# motor_driver_module.net
KiCad netlist of a schematic drawn in EAGLE
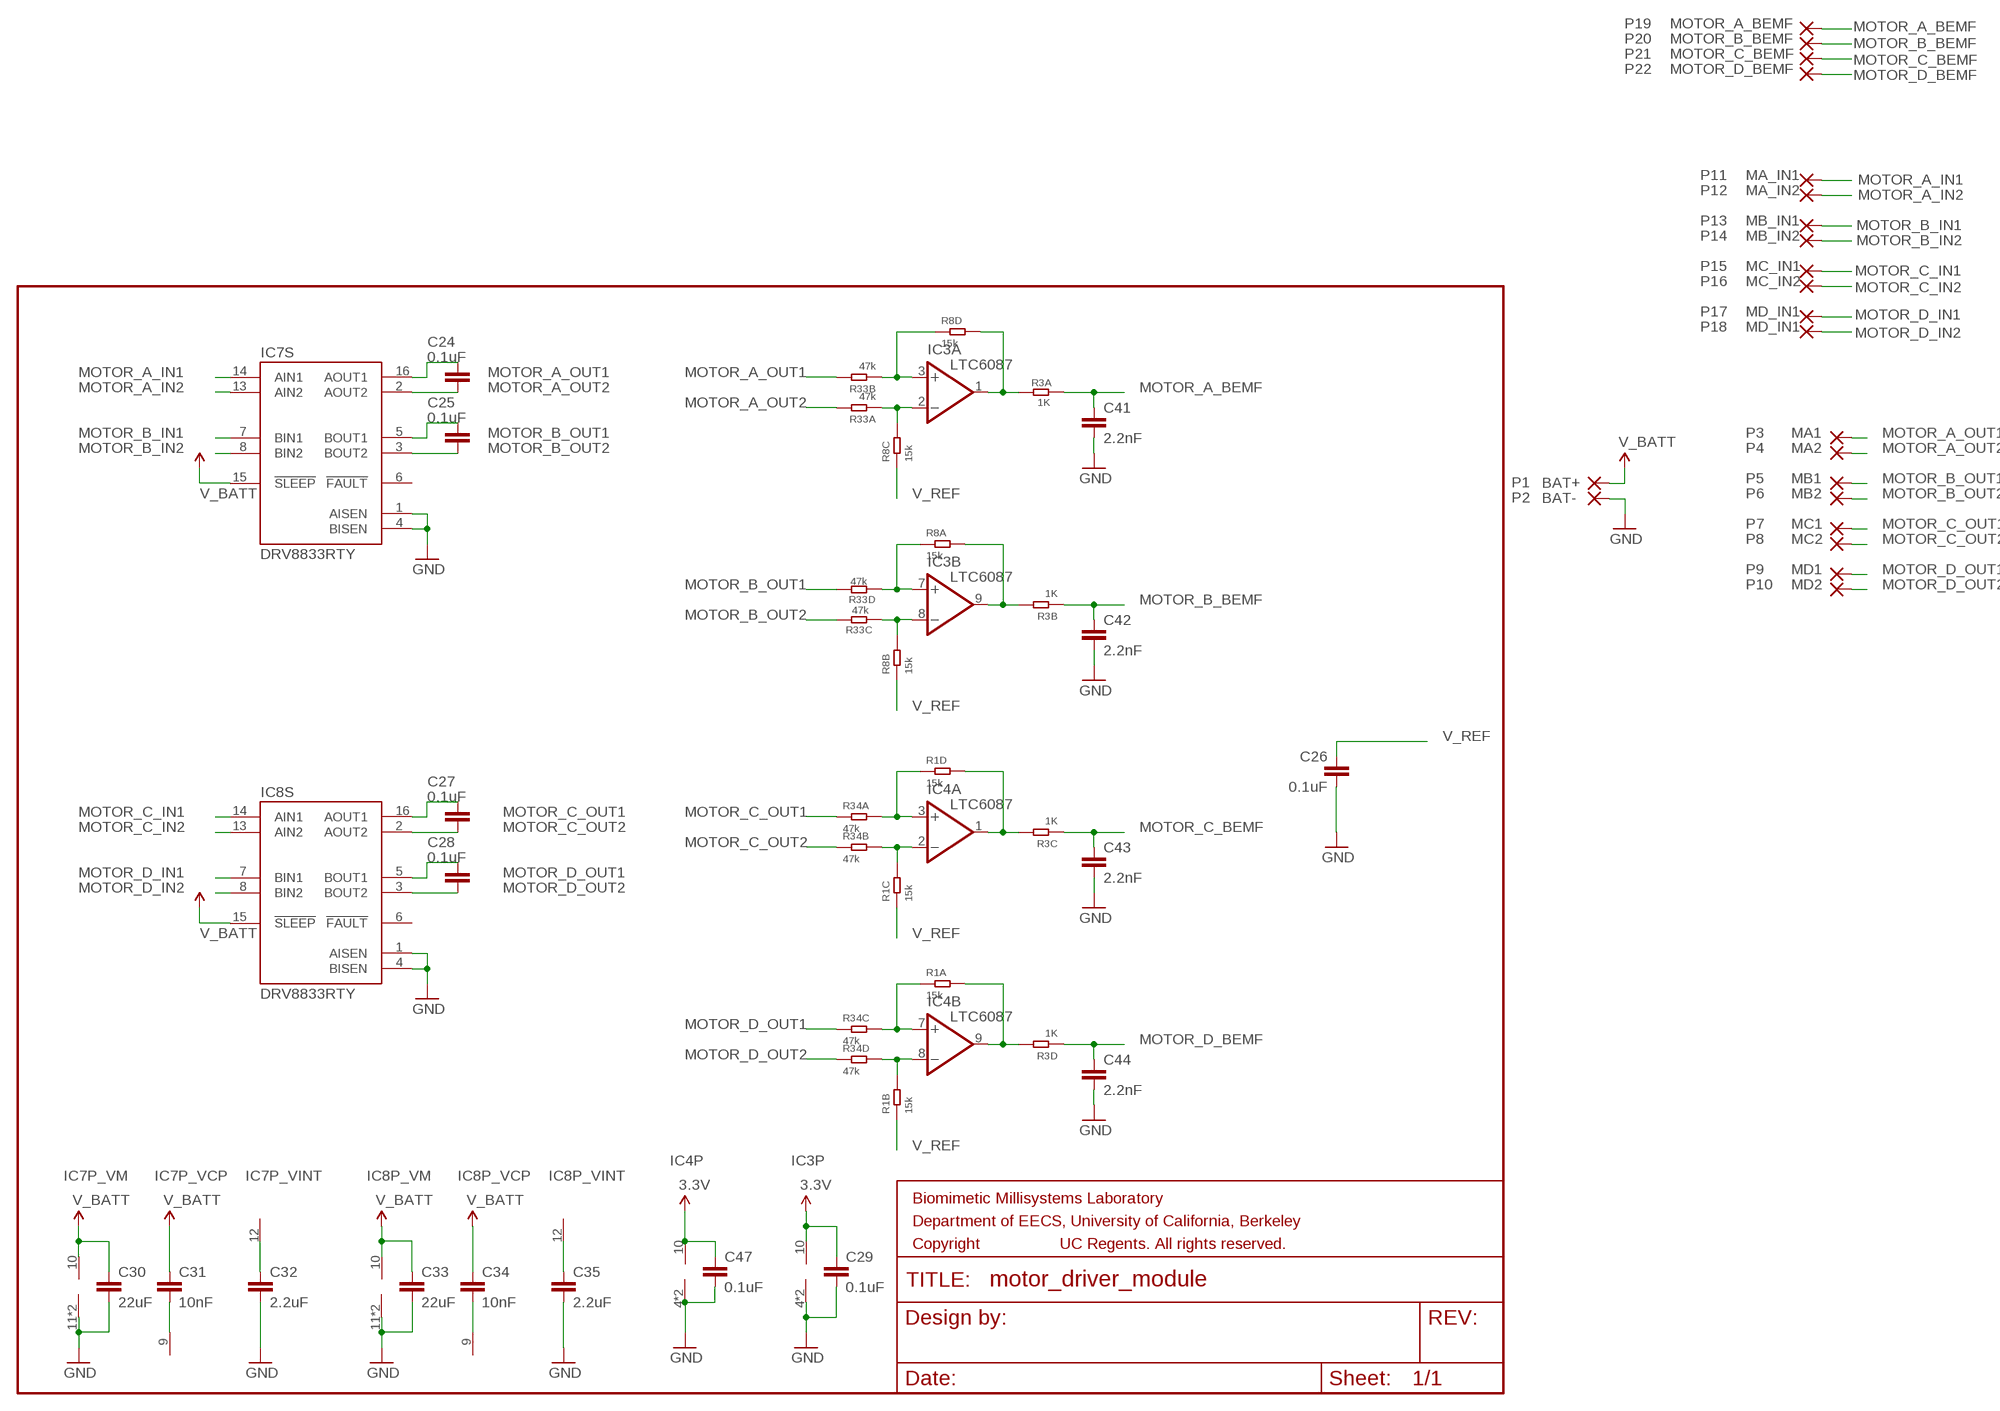
[diagram p0: schematic, sheet 1]

(export (version "E")
  (design (tool "Eeschema 10.0.6"))
  (components
    (comp (ref "C24")
      (value "0.1uF")
      (footprint "eagle-import:0402-CAP")
      (fields (field (name "VOLTAGE") "10V"))
      (libsource (lib "eagle-import") (part "CAP0402-CAP"))
    )
    (comp (ref "C25")
      (value "0.1uF")
      (footprint "eagle-import:0402-CAP")
      (fields (field (name "VOLTAGE") "10V"))
      (libsource (lib "eagle-import") (part "CAP0402-CAP"))
    )
    (comp (ref "C26")
      (value "0.1uF")
      (footprint "eagle-import:0402-CAP")
      (libsource (lib "eagle-import") (part "CAP0402-CAP"))
    )
    (comp (ref "C27")
      (value "0.1uF")
      (footprint "eagle-import:0402-CAP")
      (fields (field (name "VOLTAGE") "10V"))
      (libsource (lib "eagle-import") (part "CAP0402-CAP"))
    )
    (comp (ref "C28")
      (value "0.1uF")
      (footprint "eagle-import:0402-CAP")
      (fields (field (name "VOLTAGE") "10V"))
      (libsource (lib "eagle-import") (part "CAP0402-CAP"))
    )
    (comp (ref "C29")
      (value "0.1uF")
      (footprint "eagle-import:0402-CAP")
      (libsource (lib "eagle-import") (part "CAP0402-CAP"))
    )
    (comp (ref "C30")
      (value "22uF")
      (footprint "eagle-import:0603-CAP")
      (libsource (lib "eagle-import") (part "CAP0603-CAP"))
    )
    (comp (ref "C31")
      (value "10nF")
      (footprint "eagle-import:0402-CAP")
      (fields (field (name "VOLTAGE") "16V"))
      (libsource (lib "eagle-import") (part "CAP0402-CAP"))
    )
    (comp (ref "C32")
      (value "2.2uF")
      (footprint "eagle-import:0402-CAP")
      (fields (field (name "VOLTAGE") "6.3V"))
      (libsource (lib "eagle-import") (part "CAP0402-CAP"))
    )
    (comp (ref "C33")
      (value "22uF")
      (footprint "eagle-import:0603-CAP")
      (libsource (lib "eagle-import") (part "CAP0603-CAP"))
    )
    (comp (ref "C34")
      (value "10nF")
      (footprint "eagle-import:0402-CAP")
      (fields (field (name "VOLTAGE") "16V"))
      (libsource (lib "eagle-import") (part "CAP0402-CAP"))
    )
    (comp (ref "C35")
      (value "2.2uF")
      (footprint "eagle-import:0402-CAP")
      (fields (field (name "VOLTAGE") "6.3V"))
      (libsource (lib "eagle-import") (part "CAP0402-CAP"))
    )
    (comp (ref "C41")
      (value "2.2nF")
      (footprint "eagle-import:0402-CAP")
      (libsource (lib "eagle-import") (part "CAP0402-CAP"))
    )
    (comp (ref "C42")
      (value "2.2nF")
      (footprint "eagle-import:0402-CAP")
      (libsource (lib "eagle-import") (part "CAP0402-CAP"))
    )
    (comp (ref "C43")
      (value "2.2nF")
      (footprint "eagle-import:0402-CAP")
      (libsource (lib "eagle-import") (part "CAP0402-CAP"))
    )
    (comp (ref "C44")
      (value "2.2nF")
      (footprint "eagle-import:0402-CAP")
      (libsource (lib "eagle-import") (part "CAP0402-CAP"))
    )
    (comp (ref "C47")
      (value "0.1uF")
      (footprint "eagle-import:0402-CAP")
      (libsource (lib "eagle-import") (part "CAP0402-CAP"))
    )
    (comp (ref "IC3")
      (value "LTC6087")
      (footprint "eagle-import:DFN-10")
      (libsource (lib "eagle-import") (part "LTC6087"))
    )
    (comp (ref "IC4")
      (value "LTC6087")
      (footprint "eagle-import:DFN-10")
      (libsource (lib "eagle-import") (part "LTC6087"))
    )
    (comp (ref "IC7")
      (value "DRV8833RTY")
      (footprint "eagle-import:S-PWQFN-N16")
      (libsource (lib "eagle-import") (part "DRV8833RTY"))
    )
    (comp (ref "IC8")
      (value "DRV8833RTY")
      (footprint "eagle-import:S-PWQFN-N16")
      (libsource (lib "eagle-import") (part "DRV8833RTY"))
    )
    (comp (ref "P1")
      (value "BAT+")
      (footprint "eagle-import:SMD1,27-2,54")
      (libsource (lib "eagle-import") (part "SMD2"))
    )
    (comp (ref "P2")
      (value "BAT-")
      (footprint "eagle-import:SMD1,27-2,54")
      (libsource (lib "eagle-import") (part "SMD2"))
    )
    (comp (ref "P3")
      (value "MA1")
      (footprint "eagle-import:SMD1,27-2,54")
      (libsource (lib "eagle-import") (part "SMD2"))
    )
    (comp (ref "P4")
      (value "MA2")
      (footprint "eagle-import:SMD1,27-2,54")
      (libsource (lib "eagle-import") (part "SMD2"))
    )
    (comp (ref "P5")
      (value "MB1")
      (footprint "eagle-import:SMD1,27-2,54")
      (libsource (lib "eagle-import") (part "SMD2"))
    )
    (comp (ref "P6")
      (value "MB2")
      (footprint "eagle-import:SMD1,27-2,54")
      (libsource (lib "eagle-import") (part "SMD2"))
    )
    (comp (ref "P7")
      (value "MC1")
      (footprint "eagle-import:SMD1,27-2,54")
      (libsource (lib "eagle-import") (part "SMD2"))
    )
    (comp (ref "P8")
      (value "MC2")
      (footprint "eagle-import:SMD1,27-2,54")
      (libsource (lib "eagle-import") (part "SMD2"))
    )
    (comp (ref "P9")
      (value "MD1")
      (footprint "eagle-import:SMD1,27-2,54")
      (libsource (lib "eagle-import") (part "SMD2"))
    )
    (comp (ref "P10")
      (value "MD2")
      (footprint "eagle-import:SMD1,27-2,54")
      (libsource (lib "eagle-import") (part "SMD2"))
    )
    (comp (ref "P11")
      (value "MA_IN1")
      (footprint "eagle-import:SMD1,27-2,54")
      (libsource (lib "eagle-import") (part "SMD2"))
    )
    (comp (ref "P12")
      (value "MA_IN2")
      (footprint "eagle-import:SMD1,27-2,54")
      (libsource (lib "eagle-import") (part "SMD2"))
    )
    (comp (ref "P13")
      (value "MB_IN1")
      (footprint "eagle-import:SMD1,27-2,54")
      (libsource (lib "eagle-import") (part "SMD2"))
    )
    (comp (ref "P14")
      (value "MB_IN2")
      (footprint "eagle-import:SMD1,27-2,54")
      (libsource (lib "eagle-import") (part "SMD2"))
    )
    (comp (ref "P15")
      (value "MC_IN1")
      (footprint "eagle-import:SMD1,27-2,54")
      (libsource (lib "eagle-import") (part "SMD2"))
    )
    (comp (ref "P16")
      (value "MC_IN2")
      (footprint "eagle-import:SMD1,27-2,54")
      (libsource (lib "eagle-import") (part "SMD2"))
    )
    (comp (ref "P17")
      (value "MD_IN1")
      (footprint "eagle-import:SMD1,27-2,54")
      (libsource (lib "eagle-import") (part "SMD2"))
    )
    (comp (ref "P18")
      (value "MD_IN1")
      (footprint "eagle-import:SMD1,27-2,54")
      (libsource (lib "eagle-import") (part "SMD2"))
    )
    (comp (ref "P19")
      (value "MOTOR_A_BEMF")
      (footprint "eagle-import:SMD1,27-2,54")
      (libsource (lib "eagle-import") (part "SMD2"))
    )
    (comp (ref "P20")
      (value "MOTOR_B_BEMF")
      (footprint "eagle-import:SMD1,27-2,54")
      (libsource (lib "eagle-import") (part "SMD2"))
    )
    (comp (ref "P21")
      (value "MOTOR_C_BEMF")
      (footprint "eagle-import:SMD1,27-2,54")
      (libsource (lib "eagle-import") (part "SMD2"))
    )
    (comp (ref "P22")
      (value "MOTOR_D_BEMF")
      (footprint "eagle-import:SMD1,27-2,54")
      (libsource (lib "eagle-import") (part "SMD2"))
    )
    (comp (ref "R1")
      (value "15k")
      (footprint "eagle-import:R1206-8")
      (libsource (lib "eagle-import") (part "R-4R"))
    )
    (comp (ref "R3")
      (value "1K")
      (footprint "eagle-import:R1206-8")
      (libsource (lib "eagle-import") (part "R-4R"))
    )
    (comp (ref "R8")
      (value "15k")
      (footprint "eagle-import:R1206-8")
      (libsource (lib "eagle-import") (part "R-4R"))
    )
    (comp (ref "R33")
      (value "47k")
      (footprint "eagle-import:R1206-8")
      (libsource (lib "eagle-import") (part "R-4R"))
    )
    (comp (ref "R34")
      (value "47k")
      (footprint "eagle-import:R1206-8")
      (libsource (lib "eagle-import") (part "R-4R"))
    )
  )
  (nets
    (net (code "1") (name "/MOTOR_A_BEMF") (class "Default")
      (node (ref "C41") (pin "1") (pinfunction "1_1") (pintype "passive"))
      (node (ref "P19") (pin "1") (pinfunction "P_1") (pintype "passive"))
      (node (ref "R3") (pin "1") (pinfunction "1_1") (pintype "passive"))
    )
    (net (code "2") (name "/MOTOR_A_IN1") (class "Default")
      (node (ref "IC7") (pin "14") (pinfunction "AIN1_14") (pintype "bidirectional"))
      (node (ref "P11") (pin "1") (pinfunction "P_1") (pintype "passive"))
    )
    (net (code "3") (name "/MOTOR_A_IN2") (class "Default")
      (node (ref "IC7") (pin "13") (pinfunction "AIN2_13") (pintype "bidirectional"))
      (node (ref "P12") (pin "1") (pinfunction "P_1") (pintype "passive"))
    )
    (net (code "4") (name "/MOTOR_A_OUT1") (class "Default")
      (node (ref "C24") (pin "1") (pinfunction "1_1") (pintype "passive"))
      (node (ref "IC7") (pin "16") (pinfunction "AOUT1_16") (pintype "bidirectional"))
      (node (ref "P3") (pin "1") (pinfunction "P_1") (pintype "passive"))
      (node (ref "R33") (pin "7") (pinfunction "2_7") (pintype "passive"))
    )
    (net (code "5") (name "/MOTOR_A_OUT2") (class "Default")
      (node (ref "C24") (pin "2") (pinfunction "2_2") (pintype "passive"))
      (node (ref "IC7") (pin "2") (pinfunction "AOUT2_2") (pintype "bidirectional"))
      (node (ref "P4") (pin "1") (pinfunction "P_1") (pintype "passive"))
      (node (ref "R33") (pin "8") (pinfunction "2_8") (pintype "passive"))
    )
    (net (code "6") (name "/MOTOR_B_BEMF") (class "Default")
      (node (ref "C42") (pin "1") (pinfunction "1_1") (pintype "passive"))
      (node (ref "P20") (pin "1") (pinfunction "P_1") (pintype "passive"))
      (node (ref "R3") (pin "2") (pinfunction "1_2") (pintype "passive"))
    )
    (net (code "7") (name "/MOTOR_B_IN1") (class "Default")
      (node (ref "IC7") (pin "7") (pinfunction "BIN1_7") (pintype "bidirectional"))
      (node (ref "P13") (pin "1") (pinfunction "P_1") (pintype "passive"))
    )
    (net (code "8") (name "/MOTOR_B_IN2") (class "Default")
      (node (ref "IC7") (pin "8") (pinfunction "BIN2_8") (pintype "bidirectional"))
      (node (ref "P14") (pin "1") (pinfunction "P_1") (pintype "passive"))
    )
    (net (code "9") (name "/MOTOR_B_OUT1") (class "Default")
      (node (ref "C25") (pin "1") (pinfunction "1_1") (pintype "passive"))
      (node (ref "IC7") (pin "5") (pinfunction "BOUT1_5") (pintype "bidirectional"))
      (node (ref "P5") (pin "1") (pinfunction "P_1") (pintype "passive"))
      (node (ref "R33") (pin "4") (pinfunction "1_4") (pintype "passive"))
    )
    (net (code "10") (name "/MOTOR_B_OUT2") (class "Default")
      (node (ref "C25") (pin "2") (pinfunction "2_2") (pintype "passive"))
      (node (ref "IC7") (pin "3") (pinfunction "BOUT2_3") (pintype "bidirectional"))
      (node (ref "P6") (pin "1") (pinfunction "P_1") (pintype "passive"))
      (node (ref "R33") (pin "3") (pinfunction "1_3") (pintype "passive"))
    )
    (net (code "11") (name "/MOTOR_C_BEMF") (class "Default")
      (node (ref "C43") (pin "1") (pinfunction "1_1") (pintype "passive"))
      (node (ref "P21") (pin "1") (pinfunction "P_1") (pintype "passive"))
      (node (ref "R3") (pin "3") (pinfunction "1_3") (pintype "passive"))
    )
    (net (code "12") (name "/MOTOR_C_IN1") (class "Default")
      (node (ref "IC8") (pin "14") (pinfunction "AIN1_14") (pintype "bidirectional"))
      (node (ref "P15") (pin "1") (pinfunction "P_1") (pintype "passive"))
    )
    (net (code "13") (name "/MOTOR_C_IN2") (class "Default")
      (node (ref "IC8") (pin "13") (pinfunction "AIN2_13") (pintype "bidirectional"))
      (node (ref "P16") (pin "1") (pinfunction "P_1") (pintype "passive"))
    )
    (net (code "14") (name "/MOTOR_C_OUT1") (class "Default")
      (node (ref "C27") (pin "1") (pinfunction "1_1") (pintype "passive"))
      (node (ref "IC8") (pin "16") (pinfunction "AOUT1_16") (pintype "bidirectional"))
      (node (ref "P7") (pin "1") (pinfunction "P_1") (pintype "passive"))
      (node (ref "R34") (pin "1") (pinfunction "1_1") (pintype "passive"))
    )
    (net (code "15") (name "/MOTOR_C_OUT2") (class "Default")
      (node (ref "C27") (pin "2") (pinfunction "2_2") (pintype "passive"))
      (node (ref "IC8") (pin "2") (pinfunction "AOUT2_2") (pintype "bidirectional"))
      (node (ref "P8") (pin "1") (pinfunction "P_1") (pintype "passive"))
      (node (ref "R34") (pin "2") (pinfunction "1_2") (pintype "passive"))
    )
    (net (code "16") (name "/MOTOR_D_BEMF") (class "Default")
      (node (ref "C44") (pin "1") (pinfunction "1_1") (pintype "passive"))
      (node (ref "P22") (pin "1") (pinfunction "P_1") (pintype "passive"))
      (node (ref "R3") (pin "4") (pinfunction "1_4") (pintype "passive"))
    )
    (net (code "17") (name "/MOTOR_D_IN1") (class "Default")
      (node (ref "IC8") (pin "7") (pinfunction "BIN1_7") (pintype "bidirectional"))
      (node (ref "P17") (pin "1") (pinfunction "P_1") (pintype "passive"))
    )
    (net (code "18") (name "/MOTOR_D_IN2") (class "Default")
      (node (ref "IC8") (pin "8") (pinfunction "BIN2_8") (pintype "bidirectional"))
      (node (ref "P18") (pin "1") (pinfunction "P_1") (pintype "passive"))
    )
    (net (code "19") (name "/MOTOR_D_OUT1") (class "Default")
      (node (ref "C28") (pin "1") (pinfunction "1_1") (pintype "passive"))
      (node (ref "IC8") (pin "5") (pinfunction "BOUT1_5") (pintype "bidirectional"))
      (node (ref "P9") (pin "1") (pinfunction "P_1") (pintype "passive"))
      (node (ref "R34") (pin "3") (pinfunction "1_3") (pintype "passive"))
    )
    (net (code "20") (name "/MOTOR_D_OUT2") (class "Default")
      (node (ref "C28") (pin "2") (pinfunction "2_2") (pintype "passive"))
      (node (ref "IC8") (pin "3") (pinfunction "BOUT2_3") (pintype "bidirectional"))
      (node (ref "P10") (pin "1") (pinfunction "P_1") (pintype "passive"))
      (node (ref "R34") (pin "4") (pinfunction "1_4") (pintype "passive"))
    )
    (net (code "21") (name "/V_REF") (class "Default")
      (node (ref "C26") (pin "1") (pinfunction "1_1") (pintype "passive"))
      (node (ref "R1") (pin "2") (pinfunction "1_2") (pintype "passive"))
      (node (ref "R1") (pin "3") (pinfunction "1_3") (pintype "passive"))
      (node (ref "R8") (pin "2") (pinfunction "1_2") (pintype "passive"))
      (node (ref "R8") (pin "3") (pinfunction "1_3") (pintype "passive"))
    )
    (net (code "22") (name "3.3V") (class "Default")
      (node (ref "C29") (pin "1") (pinfunction "1_1") (pintype "passive"))
      (node (ref "C47") (pin "1") (pinfunction "1_1") (pintype "passive"))
      (node (ref "IC3") (pin "10") (pinfunction "V+_10") (pintype "power_in"))
      (node (ref "IC4") (pin "10") (pinfunction "V+_10") (pintype "power_in"))
    )
    (net (code "23") (name "GND") (class "Default")
      (node (ref "C26") (pin "2") (pinfunction "2_2") (pintype "passive"))
      (node (ref "C29") (pin "2") (pinfunction "2_2") (pintype "passive"))
      (node (ref "C30") (pin "2") (pinfunction "2_2") (pintype "passive"))
      (node (ref "C32") (pin "2") (pinfunction "2_2") (pintype "passive"))
      (node (ref "C33") (pin "2") (pinfunction "2_2") (pintype "passive"))
      (node (ref "C35") (pin "2") (pinfunction "2_2") (pintype "passive"))
      (node (ref "C41") (pin "2") (pinfunction "2_2") (pintype "passive"))
      (node (ref "C42") (pin "2") (pinfunction "2_2") (pintype "passive"))
      (node (ref "C43") (pin "2") (pinfunction "2_2") (pintype "passive"))
      (node (ref "C44") (pin "2") (pinfunction "2_2") (pintype "passive"))
      (node (ref "C47") (pin "2") (pinfunction "2_2") (pintype "passive"))
      (node (ref "IC3") (pin "4") (pinfunction "V-_4") (pintype "power_in"))
      (node (ref "IC3") (pin "PAD") (pinfunction "V-_PAD") (pintype "power_in"))
      (node (ref "IC4") (pin "4") (pinfunction "V-_4") (pintype "power_in"))
      (node (ref "IC4") (pin "PAD") (pinfunction "V-_PAD") (pintype "power_in"))
      (node (ref "IC7") (pin "1") (pinfunction "AISEN_1") (pintype "bidirectional"))
      (node (ref "IC7") (pin "11") (pinfunction "V-_11") (pintype "power_in"))
      (node (ref "IC7") (pin "4") (pinfunction "BISEN_4") (pintype "bidirectional"))
      (node (ref "IC7") (pin "PPAD") (pinfunction "V-_PPAD") (pintype "power_in"))
      (node (ref "IC8") (pin "1") (pinfunction "AISEN_1") (pintype "bidirectional"))
      (node (ref "IC8") (pin "11") (pinfunction "V-_11") (pintype "power_in"))
      (node (ref "IC8") (pin "4") (pinfunction "BISEN_4") (pintype "bidirectional"))
      (node (ref "IC8") (pin "PPAD") (pinfunction "V-_PPAD") (pintype "power_in"))
      (node (ref "P2") (pin "1") (pinfunction "P_1") (pintype "passive"))
    )
    (net (code "24") (name "Net-(IC3C-+IN)") (class "Default")
      (node (ref "IC3") (pin "3") (pinfunction "+IN_3") (pintype "input"))
      (node (ref "R33") (pin "2") (pinfunction "1_2") (pintype "passive"))
      (node (ref "R8") (pin "4") (pinfunction "1_4") (pintype "passive"))
    )
    (net (code "25") (name "Net-(IC3C--IN)") (class "Default")
      (node (ref "IC3") (pin "2") (pinfunction "-IN_2") (pintype "input"))
      (node (ref "R33") (pin "1") (pinfunction "1_1") (pintype "passive"))
      (node (ref "R8") (pin "6") (pinfunction "2_6") (pintype "passive"))
    )
    (net (code "26") (name "Net-(IC3C-OUT)") (class "Default")
      (node (ref "IC3") (pin "1") (pinfunction "OUT_1") (pintype "output"))
      (node (ref "R3") (pin "8") (pinfunction "2_8") (pintype "passive"))
      (node (ref "R8") (pin "5") (pinfunction "2_5") (pintype "passive"))
    )
    (net (code "27") (name "Net-(IC3D-+IN)") (class "Default")
      (node (ref "IC3") (pin "7") (pinfunction "+IN_7") (pintype "input"))
      (node (ref "R33") (pin "5") (pinfunction "2_5") (pintype "passive"))
      (node (ref "R8") (pin "1") (pinfunction "1_1") (pintype "passive"))
    )
    (net (code "28") (name "Net-(IC3D--IN)") (class "Default")
      (node (ref "IC3") (pin "8") (pinfunction "-IN_8") (pintype "input"))
      (node (ref "R33") (pin "6") (pinfunction "2_6") (pintype "passive"))
      (node (ref "R8") (pin "7") (pinfunction "2_7") (pintype "passive"))
    )
    (net (code "29") (name "Net-(IC3D-OUT)") (class "Default")
      (node (ref "IC3") (pin "9") (pinfunction "OUT_9") (pintype "output"))
      (node (ref "R3") (pin "7") (pinfunction "2_7") (pintype "passive"))
      (node (ref "R8") (pin "8") (pinfunction "2_8") (pintype "passive"))
    )
    (net (code "30") (name "Net-(IC4C-+IN)") (class "Default")
      (node (ref "IC4") (pin "3") (pinfunction "+IN_3") (pintype "input"))
      (node (ref "R1") (pin "4") (pinfunction "1_4") (pintype "passive"))
      (node (ref "R34") (pin "8") (pinfunction "2_8") (pintype "passive"))
    )
    (net (code "31") (name "Net-(IC4C--IN)") (class "Default")
      (node (ref "IC4") (pin "2") (pinfunction "-IN_2") (pintype "input"))
      (node (ref "R1") (pin "6") (pinfunction "2_6") (pintype "passive"))
      (node (ref "R34") (pin "7") (pinfunction "2_7") (pintype "passive"))
    )
    (net (code "32") (name "Net-(IC4C-OUT)") (class "Default")
      (node (ref "IC4") (pin "1") (pinfunction "OUT_1") (pintype "output"))
      (node (ref "R1") (pin "5") (pinfunction "2_5") (pintype "passive"))
      (node (ref "R3") (pin "6") (pinfunction "2_6") (pintype "passive"))
    )
    (net (code "33") (name "Net-(IC4D-+IN)") (class "Default")
      (node (ref "IC4") (pin "7") (pinfunction "+IN_7") (pintype "input"))
      (node (ref "R1") (pin "1") (pinfunction "1_1") (pintype "passive"))
      (node (ref "R34") (pin "6") (pinfunction "2_6") (pintype "passive"))
    )
    (net (code "34") (name "Net-(IC4D--IN)") (class "Default")
      (node (ref "IC4") (pin "8") (pinfunction "-IN_8") (pintype "input"))
      (node (ref "R1") (pin "7") (pinfunction "2_7") (pintype "passive"))
      (node (ref "R34") (pin "5") (pinfunction "2_5") (pintype "passive"))
    )
    (net (code "35") (name "Net-(IC4D-OUT)") (class "Default")
      (node (ref "IC4") (pin "9") (pinfunction "OUT_9") (pintype "output"))
      (node (ref "R1") (pin "8") (pinfunction "2_8") (pintype "passive"))
      (node (ref "R3") (pin "5") (pinfunction "2_5") (pintype "passive"))
    )
    (net (code "36") (name "Net-(IC7A-V+)") (class "Default")
      (node (ref "C31") (pin "2") (pinfunction "2_2") (pintype "passive"))
      (node (ref "IC7") (pin "9") (pinfunction "V+_9") (pintype "power_in"))
    )
    (net (code "37") (name "Net-(IC7B-V-)") (class "Default")
      (node (ref "C32") (pin "1") (pinfunction "1_1") (pintype "passive"))
      (node (ref "IC7") (pin "12") (pinfunction "V-_12") (pintype "power_in"))
    )
    (net (code "38") (name "Net-(IC8A-V+)") (class "Default")
      (node (ref "C34") (pin "2") (pinfunction "2_2") (pintype "passive"))
      (node (ref "IC8") (pin "9") (pinfunction "V+_9") (pintype "power_in"))
    )
    (net (code "39") (name "Net-(IC8B-V-)") (class "Default")
      (node (ref "C35") (pin "1") (pinfunction "1_1") (pintype "passive"))
      (node (ref "IC8") (pin "12") (pinfunction "V-_12") (pintype "power_in"))
    )
    (net (code "40") (name "V_BATT") (class "Default")
      (node (ref "C30") (pin "1") (pinfunction "1_1") (pintype "passive"))
      (node (ref "C31") (pin "1") (pinfunction "1_1") (pintype "passive"))
      (node (ref "C33") (pin "1") (pinfunction "1_1") (pintype "passive"))
      (node (ref "C34") (pin "1") (pinfunction "1_1") (pintype "passive"))
      (node (ref "IC7") (pin "10") (pinfunction "V+_10") (pintype "power_in"))
      (node (ref "IC7") (pin "15") (pinfunction "~{SLEEP}_15") (pintype "bidirectional"))
      (node (ref "IC8") (pin "10") (pinfunction "V+_10") (pintype "power_in"))
      (node (ref "IC8") (pin "15") (pinfunction "~{SLEEP}_15") (pintype "bidirectional"))
      (node (ref "P1") (pin "1") (pinfunction "P_1") (pintype "passive"))
    )
    (net (code "41") (name "unconnected-(IC7D-~{FAULT}-Pad6)") (class "Default")
      (node (ref "IC7") (pin "6") (pinfunction "~{FAULT}_6") (pintype "bidirectional"))
    )
    (net (code "42") (name "unconnected-(IC8D-~{FAULT}-Pad6)") (class "Default")
      (node (ref "IC8") (pin "6") (pinfunction "~{FAULT}_6") (pintype "bidirectional"))
    )
  )
)
